# prototype.net
KiCad netlist of a schematic drawn in EAGLE
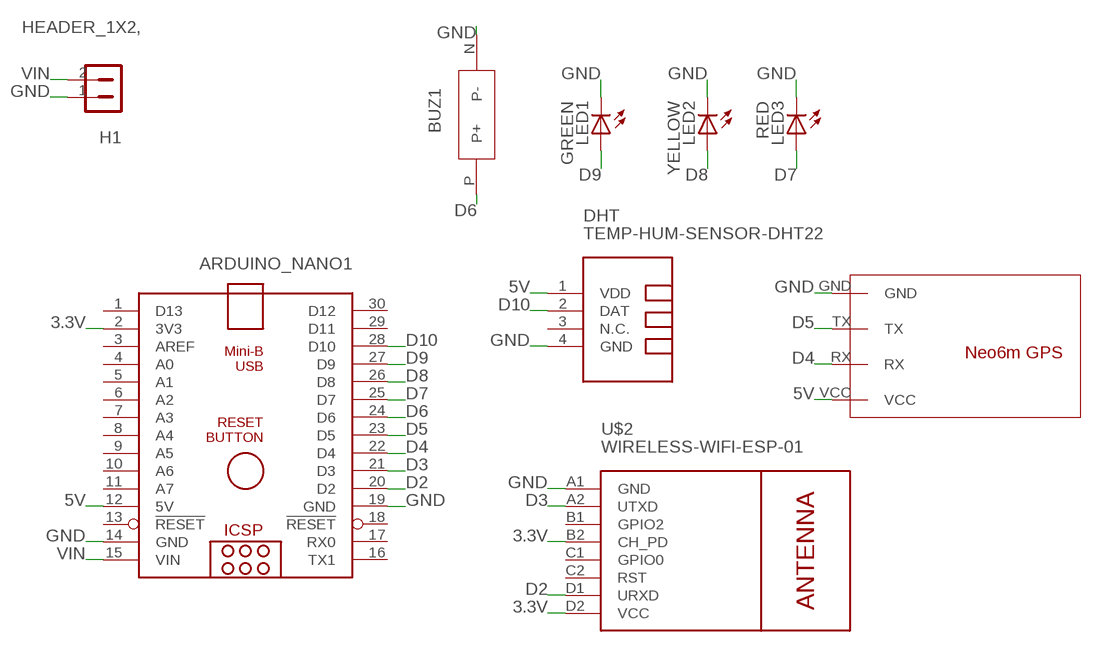
[diagram p0: schematic, sheet 1]

(export (version "E")
  (design (tool "Eeschema 10.0.6"))
  (components
    (comp (ref "ARDUINO_NANO1")
      (value "ARDUINO_NANO")
      (footprint "eagle-import:ARDUINO_NANO")
      (libsource (lib "eagle-import") (part "ARDUINO_NANO"))
    )
    (comp (ref "BUZ1")
      (value "BUZZER")
      (footprint "eagle-import:BUZZER")
      (libsource (lib "eagle-import") (part "BUZZER"))
    )
    (comp (ref "DHT")
      (value "TEMP-HUM-SENSOR-DHT22")
      (footprint "eagle-import:TEMP-HUM-SENSOR-DHT22")
      (libsource (lib "eagle-import") (part "TEMP-HUM-SENSOR-DHT22"))
    )
    (comp (ref "H1")
      (value "HEADER_1X2,")
      (footprint "eagle-import:MA_2X1")
      (fields (field (name "MANUFACTURER_PART_NUMBER") "M20-9990246"))
      (libsource (lib "eagle-import") (part "HEADER_1X2,"))
    )
    (comp (ref "LED1")
      (value "GREEN")
      (footprint "eagle-import:LED5MM")
      (libsource (lib "eagle-import") (part "LED5MM"))
    )
    (comp (ref "LED2")
      (value "YELLOW")
      (footprint "eagle-import:LED5MM")
      (libsource (lib "eagle-import") (part "LED5MM"))
    )
    (comp (ref "LED3")
      (value "RED")
      (footprint "eagle-import:LED5MM")
      (libsource (lib "eagle-import") (part "LED5MM"))
    )
    (comp (ref "U$1")
      (value "NEO6M")
      (footprint "eagle-import:NEO6M")
      (libsource (lib "eagle-import") (part "NEO6M"))
    )
    (comp (ref "U$2")
      (value "WIRELESS-WIFI-ESP-01")
      (footprint "eagle-import:WIRELESS-WIFI-ESP-01")
      (libsource (lib "eagle-import") (part "WIRELESS-WIFI-ESP-01"))
    )
  )
  (nets
    (net (code "1") (name "/3.3V") (class "Default")
      (node (ref "ARDUINO_NANO1") (pin "2") (pinfunction "3V3_2") (pintype "output"))
      (node (ref "U$2") (pin "B2") (pinfunction "CH_PD_B2") (pintype "bidirectional"))
      (node (ref "U$2") (pin "D2") (pinfunction "VCC_D2") (pintype "power_in"))
    )
    (net (code "2") (name "/5V") (class "Default")
      (node (ref "ARDUINO_NANO1") (pin "12") (pinfunction "5V_12") (pintype "power_in"))
      (node (ref "DHT") (pin "1") (pinfunction "VDD_1") (pintype "power_in"))
      (node (ref "U$1") (pin "VCC") (pinfunction "VCC_VCC") (pintype "bidirectional"))
    )
    (net (code "3") (name "/D2") (class "Default")
      (node (ref "ARDUINO_NANO1") (pin "20") (pinfunction "D2_20") (pintype "bidirectional"))
      (node (ref "U$2") (pin "D1") (pinfunction "URXD_D1") (pintype "bidirectional"))
    )
    (net (code "4") (name "/D3") (class "Default")
      (node (ref "ARDUINO_NANO1") (pin "21") (pinfunction "D3_21") (pintype "bidirectional"))
      (node (ref "U$2") (pin "A2") (pinfunction "UTXD_A2") (pintype "bidirectional"))
    )
    (net (code "5") (name "/D4") (class "Default")
      (node (ref "ARDUINO_NANO1") (pin "22") (pinfunction "D4_22") (pintype "bidirectional"))
      (node (ref "U$1") (pin "RX") (pinfunction "RX_RX") (pintype "bidirectional"))
    )
    (net (code "6") (name "/D5") (class "Default")
      (node (ref "ARDUINO_NANO1") (pin "23") (pinfunction "D5_23") (pintype "bidirectional"))
      (node (ref "U$1") (pin "TX") (pinfunction "TX_TX") (pintype "bidirectional"))
    )
    (net (code "7") (name "/D6") (class "Default")
      (node (ref "ARDUINO_NANO1") (pin "24") (pinfunction "D6_24") (pintype "bidirectional"))
      (node (ref "BUZ1") (pin "P") (pinfunction "P+_P") (pintype "bidirectional"))
    )
    (net (code "8") (name "/D7") (class "Default")
      (node (ref "ARDUINO_NANO1") (pin "25") (pinfunction "D7_25") (pintype "bidirectional"))
      (node (ref "LED3") (pin "A") (pinfunction "A_A") (pintype "passive"))
    )
    (net (code "9") (name "/D8") (class "Default")
      (node (ref "ARDUINO_NANO1") (pin "26") (pinfunction "D8_26") (pintype "bidirectional"))
      (node (ref "LED2") (pin "A") (pinfunction "A_A") (pintype "passive"))
    )
    (net (code "10") (name "/D9") (class "Default")
      (node (ref "ARDUINO_NANO1") (pin "27") (pinfunction "D9_27") (pintype "bidirectional"))
      (node (ref "LED1") (pin "A") (pinfunction "A_A") (pintype "passive"))
    )
    (net (code "11") (name "/D10") (class "Default")
      (node (ref "ARDUINO_NANO1") (pin "28") (pinfunction "D10_28") (pintype "bidirectional"))
      (node (ref "DHT") (pin "2") (pinfunction "DAT_2") (pintype "bidirectional"))
    )
    (net (code "12") (name "/GND") (class "Default")
      (node (ref "ARDUINO_NANO1") (pin "14") (pinfunction "GND_14") (pintype "power_in"))
      (node (ref "ARDUINO_NANO1") (pin "19") (pinfunction "GND_19") (pintype "power_in"))
      (node (ref "BUZ1") (pin "N") (pinfunction "P-_N") (pintype "bidirectional"))
      (node (ref "DHT") (pin "4") (pinfunction "GND_4") (pintype "power_in"))
      (node (ref "H1") (pin "1") (pinfunction "1_1") (pintype "passive"))
      (node (ref "LED1") (pin "K") (pinfunction "C_K") (pintype "passive"))
      (node (ref "LED2") (pin "K") (pinfunction "C_K") (pintype "passive"))
      (node (ref "LED3") (pin "K") (pinfunction "C_K") (pintype "passive"))
      (node (ref "U$1") (pin "GND") (pinfunction "GND_GND") (pintype "bidirectional"))
      (node (ref "U$2") (pin "A1") (pinfunction "GND_A1") (pintype "power_in"))
    )
    (net (code "13") (name "/VIN") (class "Default")
      (node (ref "ARDUINO_NANO1") (pin "15") (pinfunction "VIN_15") (pintype "power_in"))
      (node (ref "H1") (pin "2") (pinfunction "2_2") (pintype "passive"))
    )
    (net (code "14") (name "unconnected-(ARDUINO_NANO1-A0-Pad4)") (class "Default")
      (node (ref "ARDUINO_NANO1") (pin "4") (pinfunction "A0_4") (pintype "bidirectional"))
    )
    (net (code "15") (name "unconnected-(ARDUINO_NANO1-A1-Pad5)") (class "Default")
      (node (ref "ARDUINO_NANO1") (pin "5") (pinfunction "A1_5") (pintype "bidirectional"))
    )
    (net (code "16") (name "unconnected-(ARDUINO_NANO1-A2-Pad6)") (class "Default")
      (node (ref "ARDUINO_NANO1") (pin "6") (pinfunction "A2_6") (pintype "bidirectional"))
    )
    (net (code "17") (name "unconnected-(ARDUINO_NANO1-A3-Pad7)") (class "Default")
      (node (ref "ARDUINO_NANO1") (pin "7") (pinfunction "A3_7") (pintype "bidirectional"))
    )
    (net (code "18") (name "unconnected-(ARDUINO_NANO1-A4-Pad8)") (class "Default")
      (node (ref "ARDUINO_NANO1") (pin "8") (pinfunction "A4_8") (pintype "bidirectional"))
    )
    (net (code "19") (name "unconnected-(ARDUINO_NANO1-A5-Pad9)") (class "Default")
      (node (ref "ARDUINO_NANO1") (pin "9") (pinfunction "A5_9") (pintype "bidirectional"))
    )
    (net (code "20") (name "unconnected-(ARDUINO_NANO1-A6-Pad10)") (class "Default")
      (node (ref "ARDUINO_NANO1") (pin "10") (pinfunction "A6_10") (pintype "bidirectional"))
    )
    (net (code "21") (name "unconnected-(ARDUINO_NANO1-A7-Pad11)") (class "Default")
      (node (ref "ARDUINO_NANO1") (pin "11") (pinfunction "A7_11") (pintype "bidirectional"))
    )
    (net (code "22") (name "unconnected-(ARDUINO_NANO1-AREF-Pad3)") (class "Default")
      (node (ref "ARDUINO_NANO1") (pin "3") (pinfunction "AREF_3") (pintype "input"))
    )
    (net (code "23") (name "unconnected-(ARDUINO_NANO1-D11-Pad29)") (class "Default")
      (node (ref "ARDUINO_NANO1") (pin "29") (pinfunction "D11_29") (pintype "bidirectional"))
    )
    (net (code "24") (name "unconnected-(ARDUINO_NANO1-D12-Pad30)") (class "Default")
      (node (ref "ARDUINO_NANO1") (pin "30") (pinfunction "D12_30") (pintype "bidirectional"))
    )
    (net (code "25") (name "unconnected-(ARDUINO_NANO1-D13-Pad1)") (class "Default")
      (node (ref "ARDUINO_NANO1") (pin "1") (pinfunction "D13_1") (pintype "bidirectional"))
    )
    (net (code "26") (name "unconnected-(ARDUINO_NANO1-RX0-Pad17)") (class "Default")
      (node (ref "ARDUINO_NANO1") (pin "17") (pinfunction "RX0_17") (pintype "bidirectional"))
    )
    (net (code "27") (name "unconnected-(ARDUINO_NANO1-TX1-Pad16)") (class "Default")
      (node (ref "ARDUINO_NANO1") (pin "16") (pinfunction "TX1_16") (pintype "bidirectional"))
    )
    (net (code "28") (name "unconnected-(ARDUINO_NANO1-~{RESET}-Pad13)") (class "Default")
      (node (ref "ARDUINO_NANO1") (pin "13") (pinfunction "~{RESET}_13") (pintype "input"))
    )
    (net (code "29") (name "unconnected-(ARDUINO_NANO1-~{RESET}-Pad18)") (class "Default")
      (node (ref "ARDUINO_NANO1") (pin "18") (pinfunction "~{RESET}_18") (pintype "input"))
    )
    (net (code "30") (name "unconnected-(DHT-N.C.-Pad3)") (class "Default")
      (node (ref "DHT") (pin "3") (pinfunction "N.C._3") (pintype "passive"))
    )
    (net (code "31") (name "unconnected-(U$2-GPIO0-PadC1)") (class "Default")
      (node (ref "U$2") (pin "C1") (pinfunction "GPIO0_C1") (pintype "bidirectional"))
    )
    (net (code "32") (name "unconnected-(U$2-GPIO2-PadB1)") (class "Default")
      (node (ref "U$2") (pin "B1") (pinfunction "GPIO2_B1") (pintype "bidirectional"))
    )
    (net (code "33") (name "unconnected-(U$2-RST-PadC2)") (class "Default")
      (node (ref "U$2") (pin "C2") (pinfunction "RST_C2") (pintype "bidirectional"))
    )
  )
)
